# 7_Accumulator_Indicator.net
KiCad netlist of a schematic drawn in Altium Designer
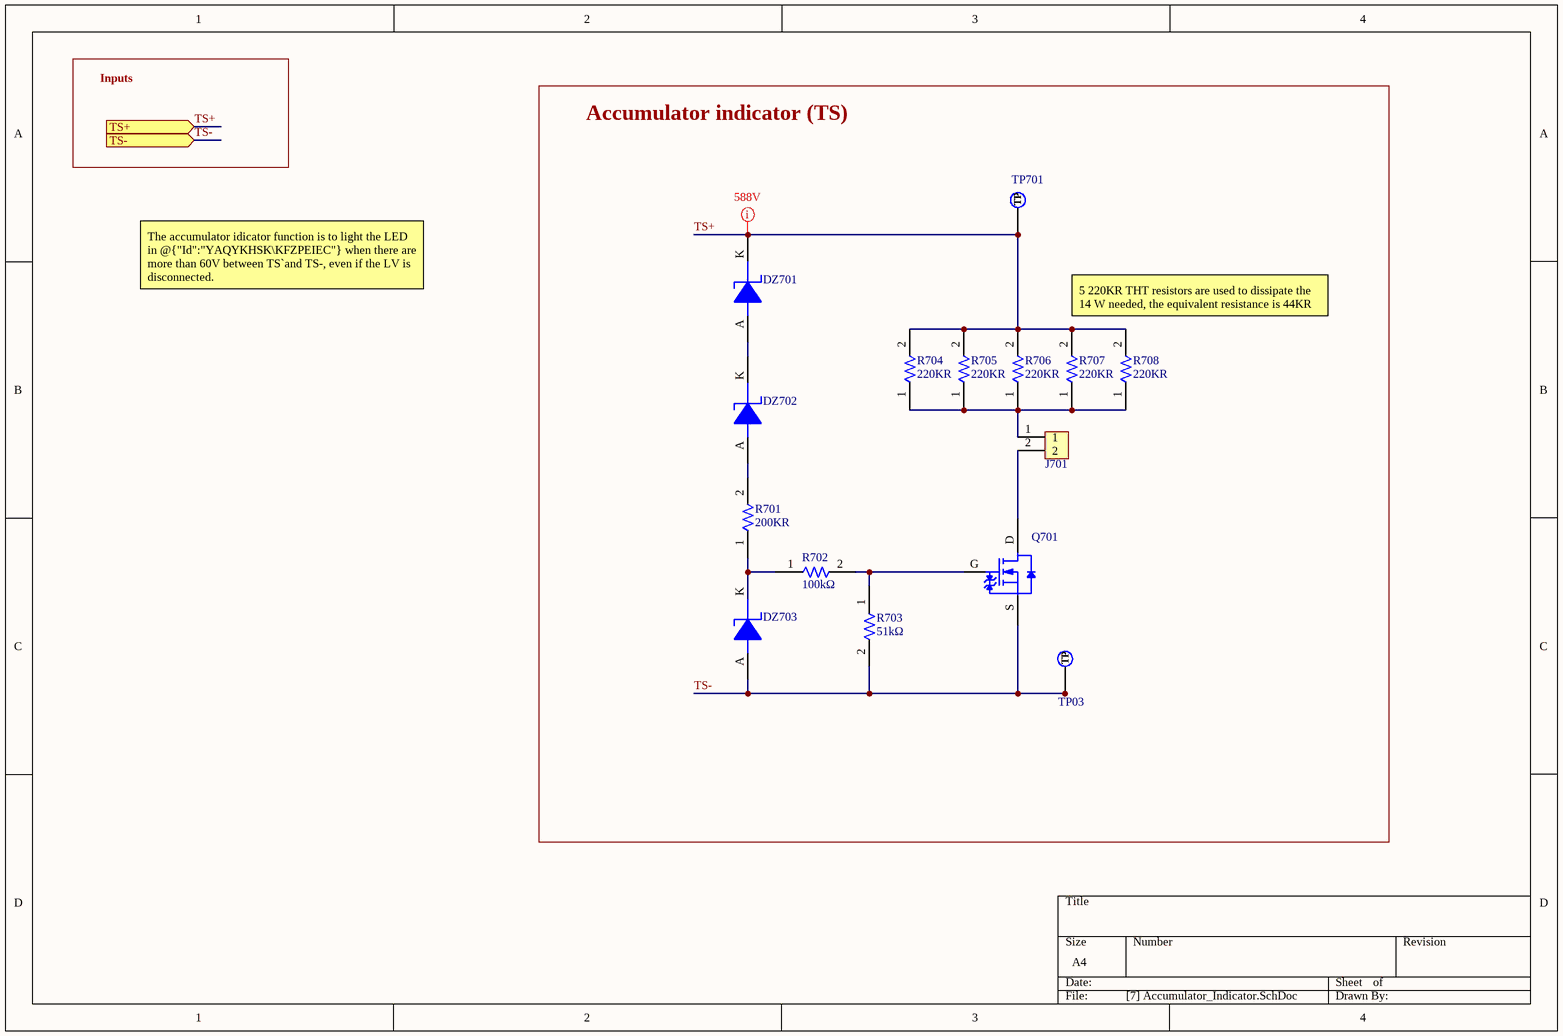
[diagram p0: [7] Accumulator_Indicator.SchDoc]

(export (version "E")
  (design (tool "Eeschema 10.0.6"))
  (components
    (comp (ref "DZ701")
      (value "DZ_24V")
      (footprint "DZ_SMB-2")
      (description "3.0 W Zener Diode Voltage Regulator 24 V (Automotive)")
      (fields
        (field (name "MANUFACTURER") "Diodes")
        (field (name "MANUFACTURER PART NUMBER") "BZT52C5V1-7-F")
      )
      (libsource (lib "Semiconductor") (part "DZ_24V"))
    )
    (comp (ref "DZ702")
      (value "DZ_24V")
      (footprint "DZ_SMB-2")
      (description "3.0 W Zener Diode Voltage Regulator 24 V (Automotive)")
      (fields
        (field (name "MANUFACTURER") "Diodes")
        (field (name "MANUFACTURER PART NUMBER") "BZT52C5V1-7-F")
      )
      (libsource (lib "Semiconductor") (part "DZ_24V"))
    )
    (comp (ref "DZ703")
      (value "DZ_10V")
      (footprint "SOD123")
      (description "BZT52C5V1 Series 500 mW 5.1 V 10 mA Surface Mount Zener Diode - SOD-123")
      (fields
        (field (name "MANUFACTURER") "Diodes")
        (field (name "MANUFACTURER PART NUMBER") "BZT52C5V1-7-F")
      )
      (libsource (lib "Semiconductor") (part "DZ_10V"))
    )
    (comp (ref "J701")
      (value "436500215")
      (footprint "J_MicroFit_2x1")
      (description "Header 1 Row Vertical Polarizing Peg 2 Pin SMT/Glow Wire Compatible Tin Plate")
      (libsource (lib "Electromechanical") (part "J_MicroFit_2x1"))
    )
    (comp (ref "Q701")
      (value "IRLR2905")
      (footprint "IRLR2905")
      (description "MOSFET N-CH 55V 42A DPAK")
      (fields
        (field (name "MANUFACTURER") "Infineon")
        (field (name "MANUFACTURER PART NUMBER") "IRLR2905TRPBF")
      )
      (libsource (lib "Semiconductor") (part "TRT-NCH-55V-42A"))
    )
    (comp (ref "R701")
      (value "200KR")
      (footprint "THT_RESISTOR")
      (libsource (lib "Passives") (part "R_200K_THT"))
    )
    (comp (ref "R702")
      (value "CRG1206F100R")
      (footprint "R1206FTK-W")
      (description "Res Thick Film 1206 100 Ohm 1% 0.25W(1/4W) ±200ppm/C Pad SMD T/R")
      (fields
        (field (name "MANUFACTURER") "TE Connectivity")
        (field (name "TOLERANCE") "1%")
        (field (name "RESISTANCE") "100kΩ")
        (field (name ".CREATOR") "AC")
      )
      (libsource (lib "Passives") (part "R100-1206FTK"))
    )
    (comp (ref "R703")
      (value "CRCW120610K0FKEA")
      (footprint "R1206FTK-W")
      (description "Res Thick Film 1206 51K Ohm 1% 1/4W ±100ppm/°C Molded SMD SMD Punched Carrier T/R")
      (fields
        (field (name "MANUFACTURER") "Panasonic")
        (field (name "MANUFACTURER PART NUMBER") "ERJ-S08F5102V")
        (field (name "RESISTANCE") "51kΩ")
        (field (name ".CREATOR") "DO")
      )
      (libsource (lib "Passives") (part "R51k-1206FTK"))
    )
    (comp (ref "R704")
      (value "220KR")
      (footprint "THT_RESISTOR")
      (libsource (lib "Passives") (part "R_220K_THT"))
    )
    (comp (ref "R705")
      (value "220KR")
      (footprint "THT_RESISTOR")
      (libsource (lib "Passives") (part "R_220K_THT"))
    )
    (comp (ref "R706")
      (value "220KR")
      (footprint "THT_RESISTOR")
      (libsource (lib "Passives") (part "R_220K_THT"))
    )
    (comp (ref "R707")
      (value "220KR")
      (footprint "THT_RESISTOR")
      (libsource (lib "Passives") (part "R_220K_THT"))
    )
    (comp (ref "R708")
      (value "220KR")
      (footprint "THT_RESISTOR")
      (libsource (lib "Passives") (part "R_220K_THT"))
    )
    (comp (ref "TP03")
      (value "TestPoint")
      (footprint "TestPoint")
      (description "Test Point 1x1 mm")
      (fields (field (name ".CREATOR") "GP") (field (name ".PCBCHECK") "GP") (field (name ".SCHCHECK") "GP"))
      (libsource (lib "e-Tech_Racing") (part "TestPoint"))
    )
    (comp (ref "TP701")
      (value "TestPoint")
      (footprint "TestPoint")
      (description "Test Point 1x1 mm")
      (fields (field (name ".CREATOR") "GP") (field (name ".PCBCHECK") "GP") (field (name ".SCHCHECK") "GP"))
      (libsource (lib "e-Tech_Racing") (part "TestPoint"))
    )
  )
  (nets
    (net (code "1") (name "/TS+") (class "Default")
      (node (ref "DZ701") (pin "K") (pinfunction "K_K") (pintype "passive"))
      (node (ref "R704") (pin "2") (pinfunction "2_2") (pintype "passive"))
      (node (ref "R705") (pin "2") (pinfunction "2_2") (pintype "passive"))
      (node (ref "R706") (pin "2") (pinfunction "2_2") (pintype "passive"))
      (node (ref "R707") (pin "2") (pinfunction "2_2") (pintype "passive"))
      (node (ref "R708") (pin "2") (pinfunction "2_2") (pintype "passive"))
      (node (ref "TP701") (pin "1") (pinfunction "TP_1") (pintype "passive"))
    )
    (net (code "2") (name "/TS-") (class "Default")
      (node (ref "DZ703") (pin "A") (pinfunction "A_A") (pintype "passive"))
      (node (ref "Q701") (pin "S") (pinfunction "S_S") (pintype "passive"))
      (node (ref "R703") (pin "2") (pinfunction "2_2") (pintype "passive"))
      (node (ref "TP03") (pin "1") (pinfunction "TP_1") (pintype "passive"))
    )
    (net (code "3") (name "Net-(DZ701-PadA)") (class "Default")
      (node (ref "DZ701") (pin "A") (pinfunction "A_A") (pintype "passive"))
      (node (ref "DZ702") (pin "K") (pinfunction "K_K") (pintype "passive"))
    )
    (net (code "4") (name "Net-(DZ702-PadA)") (class "Default")
      (node (ref "DZ702") (pin "A") (pinfunction "A_A") (pintype "passive"))
      (node (ref "R701") (pin "2") (pinfunction "2_2") (pintype "passive"))
    )
    (net (code "5") (name "Net-(DZ703-PadK)") (class "Default")
      (node (ref "DZ703") (pin "K") (pinfunction "K_K") (pintype "passive"))
      (node (ref "R701") (pin "1") (pinfunction "1_1") (pintype "passive"))
      (node (ref "R702") (pin "1") (pinfunction "1_1") (pintype "passive"))
    )
    (net (code "6") (name "Net-(J701-Pad1)") (class "Default")
      (node (ref "J701") (pin "1") (pinfunction "1_1") (pintype "passive"))
      (node (ref "R704") (pin "1") (pinfunction "1_1") (pintype "passive"))
      (node (ref "R705") (pin "1") (pinfunction "1_1") (pintype "passive"))
      (node (ref "R706") (pin "1") (pinfunction "1_1") (pintype "passive"))
      (node (ref "R707") (pin "1") (pinfunction "1_1") (pintype "passive"))
      (node (ref "R708") (pin "1") (pinfunction "1_1") (pintype "passive"))
    )
    (net (code "7") (name "Net-(J701-Pad2)") (class "Default")
      (node (ref "J701") (pin "2") (pinfunction "2_2") (pintype "passive"))
      (node (ref "Q701") (pin "D") (pinfunction "D_D") (pintype "passive"))
    )
    (net (code "8") (name "Net-(Q701-PadG)") (class "Default")
      (node (ref "Q701") (pin "G") (pinfunction "G_G") (pintype "passive"))
      (node (ref "R702") (pin "2") (pinfunction "2_2") (pintype "passive"))
      (node (ref "R703") (pin "1") (pinfunction "1_1") (pintype "passive"))
    )
  )
)
